# 328p-DIP-ISP-adapter.net
KiCad netlist of a schematic drawn in EAGLE
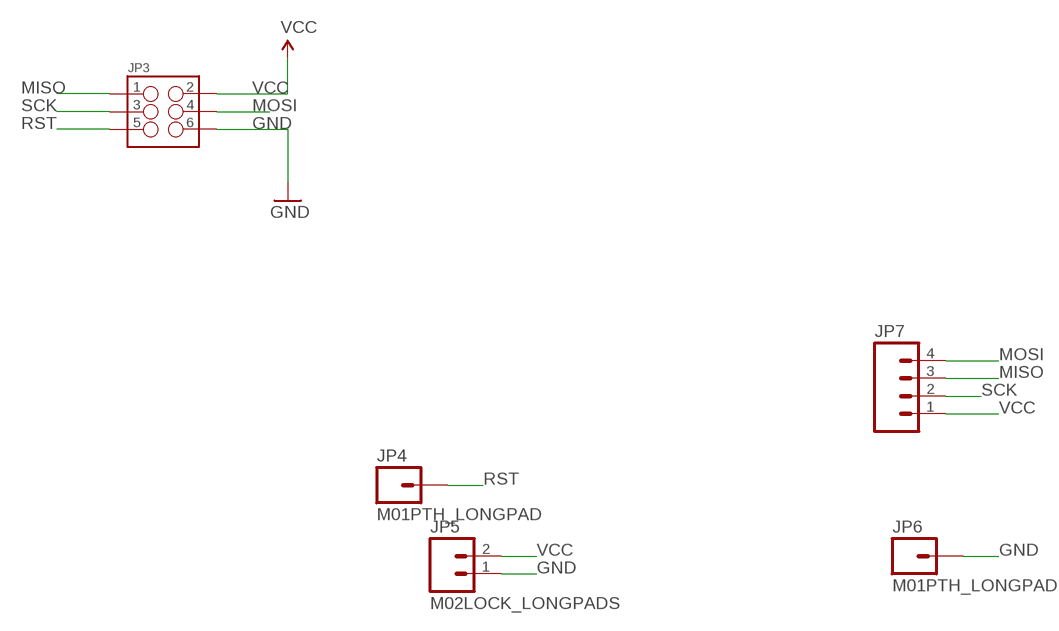
[diagram p0: schematic, sheet 1]

(export (version "E")
  (design (tool "Eeschema 10.0.6"))
  (components
    (comp (ref "JP3")
      (value "M03X2SMT")
      (footprint "eagle-import:2X3_SMT_POSTS")
      (libsource (lib "eagle-import") (part "M03X2SMT"))
    )
    (comp (ref "JP4")
      (value "M01PTH_LONGPAD")
      (footprint "eagle-import:1X01_LONGPAD")
      (libsource (lib "eagle-import") (part "M01PTH_LONGPAD"))
    )
    (comp (ref "JP5")
      (value "M02LOCK_LONGPADS")
      (footprint "eagle-import:1X02_LOCK_LONGPADS")
      (libsource (lib "eagle-import") (part "M02LOCK_LONGPADS"))
    )
    (comp (ref "JP6")
      (value "M01PTH_LONGPAD")
      (footprint "eagle-import:1X01_LONGPAD")
      (libsource (lib "eagle-import") (part "M01PTH_LONGPAD"))
    )
    (comp (ref "JP7")
      (value "M04LOCK_LONGPADS")
      (footprint "eagle-import:1X04_LOCK_LONGPADS")
      (libsource (lib "eagle-import") (part "M04LOCK_LONGPADS"))
    )
  )
  (nets
    (net (code "1") (name "/MISO") (class "Default")
      (node (ref "JP3") (pin "1") (pinfunction "1_1") (pintype "bidirectional"))
      (node (ref "JP7") (pin "3") (pinfunction "3_3") (pintype "passive"))
    )
    (net (code "2") (name "/MOSI") (class "Default")
      (node (ref "JP3") (pin "4") (pinfunction "4_4") (pintype "bidirectional"))
      (node (ref "JP7") (pin "4") (pinfunction "4_4") (pintype "passive"))
    )
    (net (code "3") (name "/RST") (class "Default")
      (node (ref "JP3") (pin "5") (pinfunction "5_5") (pintype "bidirectional"))
      (node (ref "JP4") (pin "1") (pinfunction "1_1") (pintype "passive"))
    )
    (net (code "4") (name "/SCK") (class "Default")
      (node (ref "JP3") (pin "3") (pinfunction "3_3") (pintype "bidirectional"))
      (node (ref "JP7") (pin "2") (pinfunction "2_2") (pintype "passive"))
    )
    (net (code "5") (name "GND") (class "Default")
      (node (ref "JP3") (pin "6") (pinfunction "6_6") (pintype "bidirectional"))
      (node (ref "JP5") (pin "1") (pinfunction "1_1") (pintype "passive"))
      (node (ref "JP6") (pin "1") (pinfunction "1_1") (pintype "passive"))
    )
    (net (code "6") (name "VCC") (class "Default")
      (node (ref "JP3") (pin "2") (pinfunction "2_2") (pintype "bidirectional"))
      (node (ref "JP5") (pin "2") (pinfunction "2_2") (pintype "passive"))
      (node (ref "JP7") (pin "1") (pinfunction "1_1") (pintype "passive"))
    )
  )
)
